# ProPrj_rtt_FOC_2025-11-25.net
KiCad netlist of a schematic drawn in EasyEDA Pro
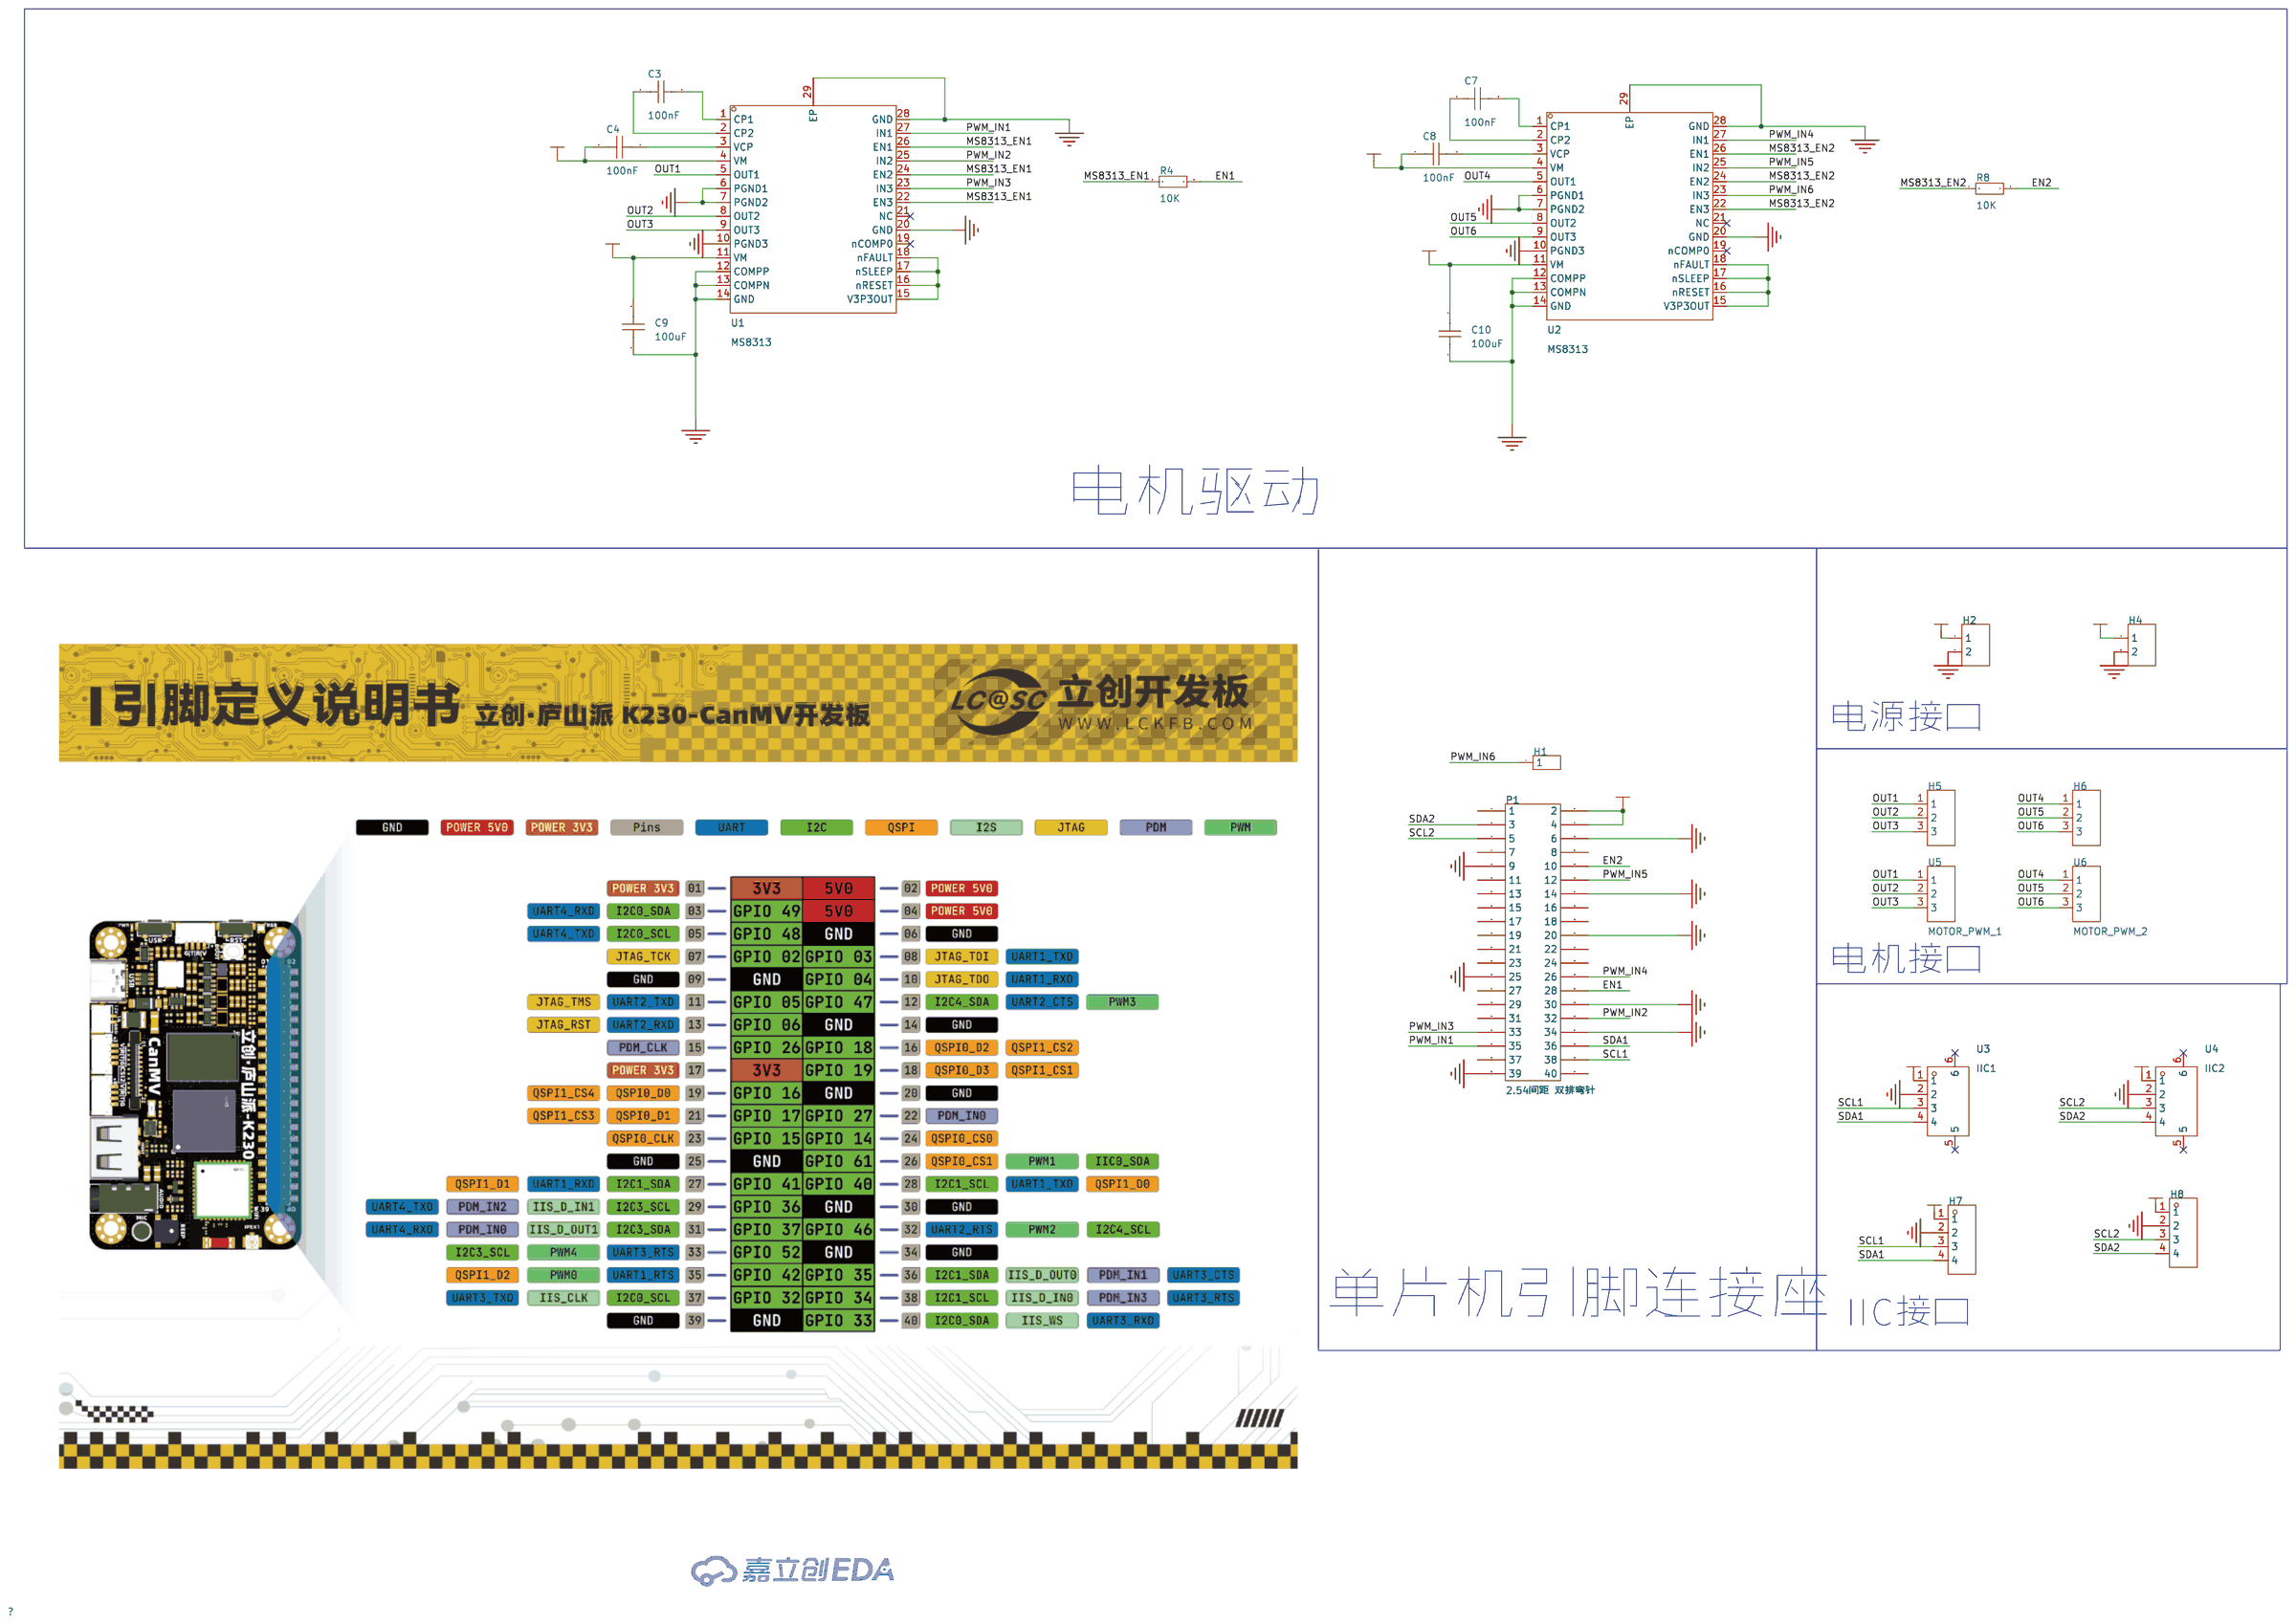
[diagram p0: schematic sheet]

(export (version "E")
  (design (tool "Eeschema 10.0.6"))
  (components
    (comp (ref "C3")
      (value "100nF")
      (footprint "easyedapro:C1206")
      (libsource (lib "easyedapro") (part "Capacitance"))
    )
    (comp (ref "C4")
      (value "100nF")
      (footprint "easyedapro:C1206")
      (libsource (lib "easyedapro") (part "Capacitance"))
    )
    (comp (ref "C7")
      (value "100nF")
      (footprint "easyedapro:C1206")
      (libsource (lib "easyedapro") (part "Capacitance"))
    )
    (comp (ref "C8")
      (value "100nF")
      (footprint "easyedapro:C1206")
      (libsource (lib "easyedapro") (part "Capacitance"))
    )
    (comp (ref "C9")
      (value "100uF")
      (footprint "easyedapro:C1206")
      (libsource (lib "easyedapro") (part "Capacitance"))
    )
    (comp (ref "C10")
      (value "100uF")
      (footprint "easyedapro:C1206")
      (libsource (lib "easyedapro") (part "Capacitance"))
    )
    (comp (ref "H1")
      (value "~")
      (footprint "easyedapro:HDR-TH_1P-V-M_XKB_X4611WV-01I-C28D40")
      (libsource (lib "easyedapro") (part "HDR_1x1"))
    )
    (comp (ref "H2")
      (value "~")
      (footprint "easyedapro:HDR-TH_2P-P2.54-V-F")
      (libsource (lib "easyedapro") (part "Header-Female-2.54_1x2"))
    )
    (comp (ref "H4")
      (value "~")
      (footprint "easyedapro:HDR-TH_2P-P2.54-V-F")
      (libsource (lib "easyedapro") (part "Header-Female-2.54_1x2"))
    )
    (comp (ref "H5")
      (value "~")
      (footprint "easyedapro:HDR-TH_3P-P2.54-V-F")
      (libsource (lib "easyedapro") (part "PM254V-11-03-H85"))
    )
    (comp (ref "H6")
      (value "~")
      (footprint "easyedapro:HDR-TH_3P-P2.54-V-F")
      (libsource (lib "easyedapro") (part "PM254V-11-03-H85"))
    )
    (comp (ref "H7")
      (value "~")
      (footprint "easyedapro:HDR-TH_4P-P2.54-V-F")
      (libsource (lib "easyedapro") (part "2.54-1*4P母"))
    )
    (comp (ref "H8")
      (value "~")
      (footprint "easyedapro:HDR-TH_4P-P2.54-V-F")
      (libsource (lib "easyedapro") (part "2.54-1*4P母"))
    )
    (comp (ref "P1")
      (value "2.54间距 双排弯针")
      (footprint "easyedapro:HDR-TH_20P-P2.54-H-R2-C10-S2.54-W12.0")
      (description "圆针/方针:-;额定电流:-;额定电压:-;配合针长度:-;塑高:-;触头材质:-;")
      (libsource (lib "easyedapro") (part "2.54pitch header"))
    )
    (comp (ref "R4") (value "10K") (footprint "easyedapro:R0603") (libsource (lib "easyedapro") (part "电阻")))
    (comp (ref "R8") (value "10K") (footprint "easyedapro:R0603") (libsource (lib "easyedapro") (part "电阻")))
    (comp (ref "U1")
      (value "MS8313")
      (footprint "easyedapro:HTSSOP-28_L9.7-W4.4-P0.65-LS6.4-BL-EP")
      (fields (field (name "Manufacturer") "杭州瑞盟"))
      (libsource (lib "easyedapro") (part "MS8313"))
    )
    (comp (ref "U2")
      (value "MS8313")
      (footprint "easyedapro:HTSSOP-28_L9.7-W4.4-P0.65-LS6.4-BL-EP")
      (fields (field (name "Manufacturer") "杭州瑞盟"))
      (libsource (lib "easyedapro") (part "MS8313"))
    )
    (comp (ref "U3")
      (value "IIC1")
      (footprint "easyedapro:CONN-SMD_4P-P1.25_XUNPU_WAFER-GH1.25-4PWB")
      (fields (field (name "Manufacturer") "XUNPU(讯普)"))
      (libsource (lib "easyedapro") (part "WAFER-GH1.25-4PWB"))
    )
    (comp (ref "U4")
      (value "IIC2")
      (footprint "easyedapro:CONN-SMD_4P-P1.25_XUNPU_WAFER-GH1.25-4PWB")
      (fields (field (name "Manufacturer") "XUNPU(讯普)"))
      (libsource (lib "easyedapro") (part "WAFER-GH1.25-4PWB"))
    )
    (comp (ref "U5")
      (value "MOTOR_PWM_1")
      (footprint "easyedapro:CONN-TH_3P-P1.25_BX-MX1.25-3PWZ")
      (libsource (lib "easyedapro") (part "BX-MX1.25-3PWZ_C9900098197"))
    )
    (comp (ref "U6")
      (value "MOTOR_PWM_2")
      (footprint "easyedapro:CONN-TH_3P-P1.25_BX-MX1.25-3PWZ")
      (libsource (lib "easyedapro") (part "BX-MX1.25-3PWZ_C9900098197"))
    )
  )
  (nets
    (net (code "1") (name "/EN1") (class "Default")
      (node (ref "P1") (pin "28") (pinfunction "28_28") (pintype "input"))
      (node (ref "R4") (pin "2") (pinfunction "2_2") (pintype "input"))
    )
    (net (code "2") (name "/EN2") (class "Default")
      (node (ref "P1") (pin "10") (pinfunction "10_10") (pintype "input"))
      (node (ref "R8") (pin "2") (pinfunction "2_2") (pintype "input"))
    )
    (net (code "3") (name "/MS8313_EN1") (class "Default")
      (node (ref "R4") (pin "1") (pinfunction "1_1") (pintype "input"))
      (node (ref "U1") (pin "22") (pinfunction "EN3_22") (pintype "unspecified"))
      (node (ref "U1") (pin "24") (pinfunction "EN2_24") (pintype "unspecified"))
      (node (ref "U1") (pin "26") (pinfunction "EN1_26") (pintype "unspecified"))
    )
    (net (code "4") (name "/MS8313_EN2") (class "Default")
      (node (ref "R8") (pin "1") (pinfunction "1_1") (pintype "input"))
      (node (ref "U2") (pin "22") (pinfunction "EN3_22") (pintype "unspecified"))
      (node (ref "U2") (pin "24") (pinfunction "EN2_24") (pintype "unspecified"))
      (node (ref "U2") (pin "26") (pinfunction "EN1_26") (pintype "unspecified"))
    )
    (net (code "5") (name "/OUT1") (class "Default")
      (node (ref "H5") (pin "1") (pinfunction "1_1") (pintype "unspecified"))
      (node (ref "U1") (pin "5") (pinfunction "OUT1_5") (pintype "unspecified"))
      (node (ref "U5") (pin "1") (pinfunction "1_1") (pintype "unspecified"))
    )
    (net (code "6") (name "/OUT2") (class "Default")
      (node (ref "H5") (pin "2") (pinfunction "2_2") (pintype "unspecified"))
      (node (ref "U1") (pin "8") (pinfunction "OUT2_8") (pintype "unspecified"))
      (node (ref "U5") (pin "2") (pinfunction "2_2") (pintype "unspecified"))
    )
    (net (code "7") (name "/OUT3") (class "Default")
      (node (ref "H5") (pin "3") (pinfunction "3_3") (pintype "unspecified"))
      (node (ref "U1") (pin "9") (pinfunction "OUT3_9") (pintype "unspecified"))
      (node (ref "U5") (pin "3") (pinfunction "3_3") (pintype "unspecified"))
    )
    (net (code "8") (name "/OUT4") (class "Default")
      (node (ref "H6") (pin "1") (pinfunction "1_1") (pintype "unspecified"))
      (node (ref "U2") (pin "5") (pinfunction "OUT1_5") (pintype "unspecified"))
      (node (ref "U6") (pin "1") (pinfunction "1_1") (pintype "unspecified"))
    )
    (net (code "9") (name "/OUT5") (class "Default")
      (node (ref "H6") (pin "2") (pinfunction "2_2") (pintype "unspecified"))
      (node (ref "U2") (pin "8") (pinfunction "OUT2_8") (pintype "unspecified"))
      (node (ref "U6") (pin "2") (pinfunction "2_2") (pintype "unspecified"))
    )
    (net (code "10") (name "/OUT6") (class "Default")
      (node (ref "H6") (pin "3") (pinfunction "3_3") (pintype "unspecified"))
      (node (ref "U2") (pin "9") (pinfunction "OUT3_9") (pintype "unspecified"))
      (node (ref "U6") (pin "3") (pinfunction "3_3") (pintype "unspecified"))
    )
    (net (code "11") (name "/PWM_IN1") (class "Default")
      (node (ref "P1") (pin "35") (pinfunction "35_35") (pintype "input"))
      (node (ref "U1") (pin "27") (pinfunction "IN1_27") (pintype "unspecified"))
    )
    (net (code "12") (name "/PWM_IN2") (class "Default")
      (node (ref "P1") (pin "32") (pinfunction "32_32") (pintype "input"))
      (node (ref "U1") (pin "25") (pinfunction "IN2_25") (pintype "unspecified"))
    )
    (net (code "13") (name "/PWM_IN3") (class "Default")
      (node (ref "P1") (pin "33") (pinfunction "33_33") (pintype "input"))
      (node (ref "U1") (pin "23") (pinfunction "IN3_23") (pintype "unspecified"))
    )
    (net (code "14") (name "/PWM_IN4") (class "Default")
      (node (ref "P1") (pin "26") (pinfunction "26_26") (pintype "input"))
      (node (ref "U2") (pin "27") (pinfunction "IN1_27") (pintype "unspecified"))
    )
    (net (code "15") (name "/PWM_IN5") (class "Default")
      (node (ref "P1") (pin "12") (pinfunction "12_12") (pintype "input"))
      (node (ref "U2") (pin "25") (pinfunction "IN2_25") (pintype "unspecified"))
    )
    (net (code "16") (name "/PWM_IN6") (class "Default")
      (node (ref "H1") (pin "1") (pinfunction "1_1") (pintype "unspecified"))
      (node (ref "U2") (pin "23") (pinfunction "IN3_23") (pintype "unspecified"))
    )
    (net (code "17") (name "/SCL1") (class "Default")
      (node (ref "H7") (pin "3") (pinfunction "3_3") (pintype "unspecified"))
      (node (ref "P1") (pin "38") (pinfunction "38_38") (pintype "input"))
      (node (ref "U3") (pin "3") (pinfunction "3_3") (pintype "unspecified"))
    )
    (net (code "18") (name "/SCL2") (class "Default")
      (node (ref "H8") (pin "3") (pinfunction "3_3") (pintype "unspecified"))
      (node (ref "P1") (pin "5") (pinfunction "5_5") (pintype "input"))
      (node (ref "U4") (pin "3") (pinfunction "3_3") (pintype "unspecified"))
    )
    (net (code "19") (name "/SDA1") (class "Default")
      (node (ref "H7") (pin "4") (pinfunction "4_4") (pintype "unspecified"))
      (node (ref "P1") (pin "36") (pinfunction "36_36") (pintype "input"))
      (node (ref "U3") (pin "4") (pinfunction "4_4") (pintype "unspecified"))
    )
    (net (code "20") (name "/SDA2") (class "Default")
      (node (ref "H8") (pin "4") (pinfunction "4_4") (pintype "unspecified"))
      (node (ref "P1") (pin "3") (pinfunction "3_3") (pintype "input"))
      (node (ref "U4") (pin "4") (pinfunction "4_4") (pintype "unspecified"))
    )
    (net (code "21") (name "5V") (class "Default")
      (node (ref "H7") (pin "1") (pinfunction "1_1") (pintype "unspecified"))
      (node (ref "H8") (pin "1") (pinfunction "1_1") (pintype "unspecified"))
      (node (ref "P1") (pin "2") (pinfunction "2_2") (pintype "input"))
      (node (ref "P1") (pin "4") (pinfunction "4_4") (pintype "input"))
      (node (ref "U3") (pin "1") (pinfunction "1_1") (pintype "unspecified"))
      (node (ref "U4") (pin "1") (pinfunction "1_1") (pintype "unspecified"))
    )
    (net (code "22") (name "12.6V") (class "Default")
      (node (ref "C10") (pin "2") (pinfunction "2_2") (pintype "input"))
      (node (ref "C4") (pin "1") (pinfunction "1_1") (pintype "input"))
      (node (ref "C8") (pin "1") (pinfunction "1_1") (pintype "input"))
      (node (ref "C9") (pin "2") (pinfunction "2_2") (pintype "input"))
      (node (ref "H2") (pin "1") (pinfunction "1_1") (pintype "input"))
      (node (ref "H4") (pin "1") (pinfunction "1_1") (pintype "input"))
      (node (ref "U1") (pin "11") (pinfunction "VM_11") (pintype "unspecified"))
      (node (ref "U1") (pin "4") (pinfunction "VM_4") (pintype "unspecified"))
      (node (ref "U2") (pin "11") (pinfunction "VM_11") (pintype "unspecified"))
      (node (ref "U2") (pin "4") (pinfunction "VM_4") (pintype "unspecified"))
    )
    (net (code "23") (name "GND") (class "Default")
      (node (ref "C10") (pin "1") (pinfunction "1_1") (pintype "input"))
      (node (ref "C9") (pin "1") (pinfunction "1_1") (pintype "input"))
      (node (ref "H2") (pin "2") (pinfunction "2_2") (pintype "input"))
      (node (ref "H4") (pin "2") (pinfunction "2_2") (pintype "input"))
      (node (ref "H7") (pin "2") (pinfunction "2_2") (pintype "unspecified"))
      (node (ref "H8") (pin "2") (pinfunction "2_2") (pintype "unspecified"))
      (node (ref "P1") (pin "14") (pinfunction "14_14") (pintype "input"))
      (node (ref "P1") (pin "20") (pinfunction "20_20") (pintype "input"))
      (node (ref "P1") (pin "25") (pinfunction "25_25") (pintype "input"))
      (node (ref "P1") (pin "30") (pinfunction "30_30") (pintype "input"))
      (node (ref "P1") (pin "34") (pinfunction "34_34") (pintype "input"))
      (node (ref "P1") (pin "39") (pinfunction "39_39") (pintype "input"))
      (node (ref "P1") (pin "6") (pinfunction "6_6") (pintype "input"))
      (node (ref "P1") (pin "9") (pinfunction "9_9") (pintype "input"))
      (node (ref "U1") (pin "10") (pinfunction "PGND3_10") (pintype "unspecified"))
      (node (ref "U1") (pin "12") (pinfunction "COMPP_12") (pintype "unspecified"))
      (node (ref "U1") (pin "13") (pinfunction "COMPN_13") (pintype "unspecified"))
      (node (ref "U1") (pin "14") (pinfunction "GND_14") (pintype "unspecified"))
      (node (ref "U1") (pin "20") (pinfunction "GND_20") (pintype "unspecified"))
      (node (ref "U1") (pin "28") (pinfunction "GND_28") (pintype "unspecified"))
      (node (ref "U1") (pin "29") (pinfunction "EP_29") (pintype "unspecified"))
      (node (ref "U1") (pin "6") (pinfunction "PGND1_6") (pintype "unspecified"))
      (node (ref "U1") (pin "7") (pinfunction "PGND2_7") (pintype "unspecified"))
      (node (ref "U2") (pin "10") (pinfunction "PGND3_10") (pintype "unspecified"))
      (node (ref "U2") (pin "12") (pinfunction "COMPP_12") (pintype "unspecified"))
      (node (ref "U2") (pin "13") (pinfunction "COMPN_13") (pintype "unspecified"))
      (node (ref "U2") (pin "14") (pinfunction "GND_14") (pintype "unspecified"))
      (node (ref "U2") (pin "20") (pinfunction "GND_20") (pintype "unspecified"))
      (node (ref "U2") (pin "28") (pinfunction "GND_28") (pintype "unspecified"))
      (node (ref "U2") (pin "29") (pinfunction "EP_29") (pintype "unspecified"))
      (node (ref "U2") (pin "6") (pinfunction "PGND1_6") (pintype "unspecified"))
      (node (ref "U2") (pin "7") (pinfunction "PGND2_7") (pintype "unspecified"))
      (node (ref "U3") (pin "2") (pinfunction "2_2") (pintype "unspecified"))
      (node (ref "U4") (pin "2") (pinfunction "2_2") (pintype "unspecified"))
    )
    (net (code "24") (name "Net-(U1-CP1)") (class "Default")
      (node (ref "C3") (pin "2") (pinfunction "2_2") (pintype "input"))
      (node (ref "U1") (pin "1") (pinfunction "CP1_1") (pintype "unspecified"))
    )
    (net (code "25") (name "Net-(U1-CP2)") (class "Default")
      (node (ref "C3") (pin "1") (pinfunction "1_1") (pintype "input"))
      (node (ref "U1") (pin "2") (pinfunction "CP2_2") (pintype "unspecified"))
    )
    (net (code "26") (name "Net-(U1-V3P3OUT)") (class "Default")
      (node (ref "U1") (pin "15") (pinfunction "V3P3OUT_15") (pintype "unspecified"))
      (node (ref "U1") (pin "16") (pinfunction "nRESET_16") (pintype "unspecified"))
      (node (ref "U1") (pin "17") (pinfunction "nSLEEP_17") (pintype "unspecified"))
      (node (ref "U1") (pin "18") (pinfunction "nFAULT_18") (pintype "unspecified"))
    )
    (net (code "27") (name "Net-(U1-VCP)") (class "Default")
      (node (ref "C4") (pin "2") (pinfunction "2_2") (pintype "input"))
      (node (ref "U1") (pin "3") (pinfunction "VCP_3") (pintype "unspecified"))
    )
    (net (code "28") (name "Net-(U2-CP1)") (class "Default")
      (node (ref "C7") (pin "2") (pinfunction "2_2") (pintype "input"))
      (node (ref "U2") (pin "1") (pinfunction "CP1_1") (pintype "unspecified"))
    )
    (net (code "29") (name "Net-(U2-CP2)") (class "Default")
      (node (ref "C7") (pin "1") (pinfunction "1_1") (pintype "input"))
      (node (ref "U2") (pin "2") (pinfunction "CP2_2") (pintype "unspecified"))
    )
    (net (code "30") (name "Net-(U2-V3P3OUT)") (class "Default")
      (node (ref "U2") (pin "15") (pinfunction "V3P3OUT_15") (pintype "unspecified"))
      (node (ref "U2") (pin "16") (pinfunction "nRESET_16") (pintype "unspecified"))
      (node (ref "U2") (pin "17") (pinfunction "nSLEEP_17") (pintype "unspecified"))
      (node (ref "U2") (pin "18") (pinfunction "nFAULT_18") (pintype "unspecified"))
    )
    (net (code "31") (name "Net-(U2-VCP)") (class "Default")
      (node (ref "C8") (pin "2") (pinfunction "2_2") (pintype "input"))
      (node (ref "U2") (pin "3") (pinfunction "VCP_3") (pintype "unspecified"))
    )
    (net (code "32") (name "unconnected-(P1-Pad1)") (class "Default")
      (node (ref "P1") (pin "1") (pinfunction "1_1") (pintype "input"))
    )
    (net (code "33") (name "unconnected-(P1-Pad7)") (class "Default")
      (node (ref "P1") (pin "7") (pinfunction "7_7") (pintype "input"))
    )
    (net (code "34") (name "unconnected-(P1-Pad8)") (class "Default")
      (node (ref "P1") (pin "8") (pinfunction "8_8") (pintype "input"))
    )
    (net (code "35") (name "unconnected-(P1-Pad11)") (class "Default")
      (node (ref "P1") (pin "11") (pinfunction "11_11") (pintype "input"))
    )
    (net (code "36") (name "unconnected-(P1-Pad13)") (class "Default")
      (node (ref "P1") (pin "13") (pinfunction "13_13") (pintype "input"))
    )
    (net (code "37") (name "unconnected-(P1-Pad15)") (class "Default")
      (node (ref "P1") (pin "15") (pinfunction "15_15") (pintype "input"))
    )
    (net (code "38") (name "unconnected-(P1-Pad16)") (class "Default")
      (node (ref "P1") (pin "16") (pinfunction "16_16") (pintype "input"))
    )
    (net (code "39") (name "unconnected-(P1-Pad17)") (class "Default")
      (node (ref "P1") (pin "17") (pinfunction "17_17") (pintype "input"))
    )
    (net (code "40") (name "unconnected-(P1-Pad18)") (class "Default")
      (node (ref "P1") (pin "18") (pinfunction "18_18") (pintype "input"))
    )
    (net (code "41") (name "unconnected-(P1-Pad19)") (class "Default")
      (node (ref "P1") (pin "19") (pinfunction "19_19") (pintype "input"))
    )
    (net (code "42") (name "unconnected-(P1-Pad21)") (class "Default")
      (node (ref "P1") (pin "21") (pinfunction "21_21") (pintype "input"))
    )
    (net (code "43") (name "unconnected-(P1-Pad22)") (class "Default")
      (node (ref "P1") (pin "22") (pinfunction "22_22") (pintype "input"))
    )
    (net (code "44") (name "unconnected-(P1-Pad23)") (class "Default")
      (node (ref "P1") (pin "23") (pinfunction "23_23") (pintype "input"))
    )
    (net (code "45") (name "unconnected-(P1-Pad24)") (class "Default")
      (node (ref "P1") (pin "24") (pinfunction "24_24") (pintype "input"))
    )
    (net (code "46") (name "unconnected-(P1-Pad27)") (class "Default")
      (node (ref "P1") (pin "27") (pinfunction "27_27") (pintype "input"))
    )
    (net (code "47") (name "unconnected-(P1-Pad29)") (class "Default")
      (node (ref "P1") (pin "29") (pinfunction "29_29") (pintype "input"))
    )
    (net (code "48") (name "unconnected-(P1-Pad31)") (class "Default")
      (node (ref "P1") (pin "31") (pinfunction "31_31") (pintype "input"))
    )
    (net (code "49") (name "unconnected-(P1-Pad37)") (class "Default")
      (node (ref "P1") (pin "37") (pinfunction "37_37") (pintype "input"))
    )
    (net (code "50") (name "unconnected-(P1-Pad40)") (class "Default")
      (node (ref "P1") (pin "40") (pinfunction "40_40") (pintype "input"))
    )
    (net (code "51") (name "unconnected-(U1-NC-Pad21)") (class "Default")
      (node (ref "U1") (pin "21") (pinfunction "NC_21") (pintype "unspecified+no_connect"))
    )
    (net (code "52") (name "unconnected-(U1-nCOMP0-Pad19)") (class "Default")
      (node (ref "U1") (pin "19") (pinfunction "nCOMP0_19") (pintype "unspecified+no_connect"))
    )
    (net (code "53") (name "unconnected-(U2-NC-Pad21)") (class "Default")
      (node (ref "U2") (pin "21") (pinfunction "NC_21") (pintype "unspecified+no_connect"))
    )
    (net (code "54") (name "unconnected-(U2-nCOMP0-Pad19)") (class "Default")
      (node (ref "U2") (pin "19") (pinfunction "nCOMP0_19") (pintype "unspecified+no_connect"))
    )
    (net (code "55") (name "unconnected-(U3-Pad5)") (class "Default")
      (node (ref "U3") (pin "5") (pinfunction "5_5") (pintype "unspecified+no_connect"))
    )
    (net (code "56") (name "unconnected-(U3-Pad6)") (class "Default")
      (node (ref "U3") (pin "6") (pinfunction "6_6") (pintype "unspecified+no_connect"))
    )
    (net (code "57") (name "unconnected-(U4-Pad5)") (class "Default")
      (node (ref "U4") (pin "5") (pinfunction "5_5") (pintype "unspecified+no_connect"))
    )
    (net (code "58") (name "unconnected-(U4-Pad6)") (class "Default")
      (node (ref "U4") (pin "6") (pinfunction "6_6") (pintype "unspecified+no_connect"))
    )
  )
)
